# enclosure_connectors_board.net
KiCad netlist of a schematic drawn in EAGLE
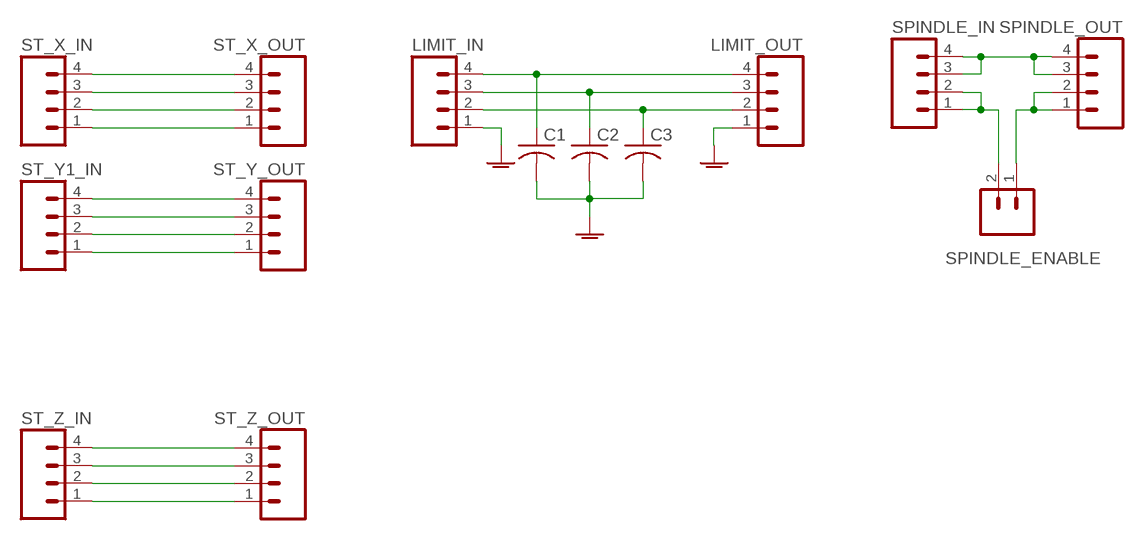
[diagram p0: schematic, sheet 1]

(export (version "E")
  (design (tool "Eeschema 10.0.6"))
  (components
    (comp (ref "C1")
      (value "C-USC0805")
      (footprint "eagle-import:C0805")
      (libsource (lib "eagle-import") (part "C-USC0805"))
    )
    (comp (ref "C2")
      (value "C-USC0805")
      (footprint "eagle-import:C0805")
      (libsource (lib "eagle-import") (part "C-USC0805"))
    )
    (comp (ref "C3")
      (value "C-USC0805")
      (footprint "eagle-import:C0805")
      (libsource (lib "eagle-import") (part "C-USC0805"))
    )
    (comp (ref "LIMIT_IN")
      (value "M04POLAR")
      (footprint "eagle-import:MOLEX-1X4")
      (libsource (lib "eagle-import") (part "M04POLAR"))
    )
    (comp (ref "LIMIT_OUT")
      (value "M04PTH")
      (footprint "eagle-import:1X04")
      (libsource (lib "eagle-import") (part "M04PTH"))
    )
    (comp (ref "SPINDLE_ENABLE")
      (value "M02LOCK_LONGPADS")
      (footprint "eagle-import:1X02_LOCK_LONGPADS")
      (libsource (lib "eagle-import") (part "M02LOCK_LONGPADS"))
    )
    (comp (ref "SPINDLE_IN")
      (value "M04PTH")
      (footprint "eagle-import:1X04")
      (libsource (lib "eagle-import") (part "M04PTH"))
    )
    (comp (ref "SPINDLE_OUT")
      (value "M04POLAR")
      (footprint "eagle-import:MOLEX-1X4")
      (libsource (lib "eagle-import") (part "M04POLAR"))
    )
    (comp (ref "ST_X_IN")
      (value "M04POLAR")
      (footprint "eagle-import:MOLEX-1X4")
      (libsource (lib "eagle-import") (part "M04POLAR"))
    )
    (comp (ref "ST_X_OUT")
      (value "M04PTH")
      (footprint "eagle-import:1X04")
      (libsource (lib "eagle-import") (part "M04PTH"))
    )
    (comp (ref "ST_Y1_IN")
      (value "M04POLAR")
      (footprint "eagle-import:MOLEX-1X4")
      (libsource (lib "eagle-import") (part "M04POLAR"))
    )
    (comp (ref "ST_Y_OUT")
      (value "M04PTH")
      (footprint "eagle-import:1X04")
      (libsource (lib "eagle-import") (part "M04PTH"))
    )
    (comp (ref "ST_Z_IN")
      (value "M04POLAR")
      (footprint "eagle-import:MOLEX-1X4")
      (libsource (lib "eagle-import") (part "M04POLAR"))
    )
    (comp (ref "ST_Z_OUT")
      (value "M04PTH")
      (footprint "eagle-import:1X04")
      (libsource (lib "eagle-import") (part "M04PTH"))
    )
  )
  (nets
    (net (code "1") (name "GNDA") (class "Default")
      (node (ref "C1") (pin "2") (pinfunction "2_2") (pintype "passive"))
      (node (ref "C2") (pin "2") (pinfunction "2_2") (pintype "passive"))
      (node (ref "C3") (pin "2") (pinfunction "2_2") (pintype "passive"))
      (node (ref "LIMIT_IN") (pin "1") (pinfunction "1_1") (pintype "passive"))
      (node (ref "LIMIT_OUT") (pin "1") (pinfunction "1_1") (pintype "passive"))
    )
    (net (code "2") (name "Net-(C1-Pad1)") (class "Default")
      (node (ref "C1") (pin "1") (pinfunction "1_1") (pintype "passive"))
      (node (ref "LIMIT_IN") (pin "4") (pinfunction "4_4") (pintype "passive"))
      (node (ref "LIMIT_OUT") (pin "4") (pinfunction "4_4") (pintype "passive"))
    )
    (net (code "3") (name "Net-(C2-Pad1)") (class "Default")
      (node (ref "C2") (pin "1") (pinfunction "1_1") (pintype "passive"))
      (node (ref "LIMIT_IN") (pin "3") (pinfunction "3_3") (pintype "passive"))
      (node (ref "LIMIT_OUT") (pin "3") (pinfunction "3_3") (pintype "passive"))
    )
    (net (code "4") (name "Net-(C3-Pad1)") (class "Default")
      (node (ref "C3") (pin "1") (pinfunction "1_1") (pintype "passive"))
      (node (ref "LIMIT_IN") (pin "2") (pinfunction "2_2") (pintype "passive"))
      (node (ref "LIMIT_OUT") (pin "2") (pinfunction "2_2") (pintype "passive"))
    )
    (net (code "5") (name "Net-(SPINDLE_ENABLE-Pad1)") (class "Default")
      (node (ref "SPINDLE_ENABLE") (pin "1") (pinfunction "1_1") (pintype "passive"))
      (node (ref "SPINDLE_OUT") (pin "1") (pinfunction "1_1") (pintype "passive"))
      (node (ref "SPINDLE_OUT") (pin "2") (pinfunction "2_2") (pintype "passive"))
    )
    (net (code "6") (name "Net-(SPINDLE_ENABLE-Pad2)") (class "Default")
      (node (ref "SPINDLE_ENABLE") (pin "2") (pinfunction "2_2") (pintype "passive"))
      (node (ref "SPINDLE_IN") (pin "1") (pinfunction "1_1") (pintype "passive"))
      (node (ref "SPINDLE_IN") (pin "2") (pinfunction "2_2") (pintype "passive"))
    )
    (net (code "7") (name "Net-(SPINDLE_IN-Pad3)") (class "Default")
      (node (ref "SPINDLE_IN") (pin "3") (pinfunction "3_3") (pintype "passive"))
      (node (ref "SPINDLE_IN") (pin "4") (pinfunction "4_4") (pintype "passive"))
      (node (ref "SPINDLE_OUT") (pin "3") (pinfunction "3_3") (pintype "passive"))
      (node (ref "SPINDLE_OUT") (pin "4") (pinfunction "4_4") (pintype "passive"))
    )
    (net (code "8") (name "Net-(ST_X_IN-Pad1)") (class "Default")
      (node (ref "ST_X_IN") (pin "1") (pinfunction "1_1") (pintype "passive"))
      (node (ref "ST_X_OUT") (pin "1") (pinfunction "1_1") (pintype "passive"))
    )
    (net (code "9") (name "Net-(ST_X_IN-Pad2)") (class "Default")
      (node (ref "ST_X_IN") (pin "2") (pinfunction "2_2") (pintype "passive"))
      (node (ref "ST_X_OUT") (pin "2") (pinfunction "2_2") (pintype "passive"))
    )
    (net (code "10") (name "Net-(ST_X_IN-Pad3)") (class "Default")
      (node (ref "ST_X_IN") (pin "3") (pinfunction "3_3") (pintype "passive"))
      (node (ref "ST_X_OUT") (pin "3") (pinfunction "3_3") (pintype "passive"))
    )
    (net (code "11") (name "Net-(ST_X_IN-Pad4)") (class "Default")
      (node (ref "ST_X_IN") (pin "4") (pinfunction "4_4") (pintype "passive"))
      (node (ref "ST_X_OUT") (pin "4") (pinfunction "4_4") (pintype "passive"))
    )
    (net (code "12") (name "Net-(ST_Y1_IN-Pad1)") (class "Default")
      (node (ref "ST_Y1_IN") (pin "1") (pinfunction "1_1") (pintype "passive"))
      (node (ref "ST_Y_OUT") (pin "1") (pinfunction "1_1") (pintype "passive"))
    )
    (net (code "13") (name "Net-(ST_Y1_IN-Pad2)") (class "Default")
      (node (ref "ST_Y1_IN") (pin "2") (pinfunction "2_2") (pintype "passive"))
      (node (ref "ST_Y_OUT") (pin "2") (pinfunction "2_2") (pintype "passive"))
    )
    (net (code "14") (name "Net-(ST_Y1_IN-Pad3)") (class "Default")
      (node (ref "ST_Y1_IN") (pin "3") (pinfunction "3_3") (pintype "passive"))
      (node (ref "ST_Y_OUT") (pin "3") (pinfunction "3_3") (pintype "passive"))
    )
    (net (code "15") (name "Net-(ST_Y1_IN-Pad4)") (class "Default")
      (node (ref "ST_Y1_IN") (pin "4") (pinfunction "4_4") (pintype "passive"))
      (node (ref "ST_Y_OUT") (pin "4") (pinfunction "4_4") (pintype "passive"))
    )
    (net (code "16") (name "Net-(ST_Z_IN-Pad1)") (class "Default")
      (node (ref "ST_Z_IN") (pin "1") (pinfunction "1_1") (pintype "passive"))
      (node (ref "ST_Z_OUT") (pin "1") (pinfunction "1_1") (pintype "passive"))
    )
    (net (code "17") (name "Net-(ST_Z_IN-Pad2)") (class "Default")
      (node (ref "ST_Z_IN") (pin "2") (pinfunction "2_2") (pintype "passive"))
      (node (ref "ST_Z_OUT") (pin "2") (pinfunction "2_2") (pintype "passive"))
    )
    (net (code "18") (name "Net-(ST_Z_IN-Pad3)") (class "Default")
      (node (ref "ST_Z_IN") (pin "3") (pinfunction "3_3") (pintype "passive"))
      (node (ref "ST_Z_OUT") (pin "3") (pinfunction "3_3") (pintype "passive"))
    )
    (net (code "19") (name "Net-(ST_Z_IN-Pad4)") (class "Default")
      (node (ref "ST_Z_IN") (pin "4") (pinfunction "4_4") (pintype "passive"))
      (node (ref "ST_Z_OUT") (pin "4") (pinfunction "4_4") (pintype "passive"))
    )
  )
)
